# MJoy16-C1.net
KiCad netlist of a schematic drawn in EAGLE
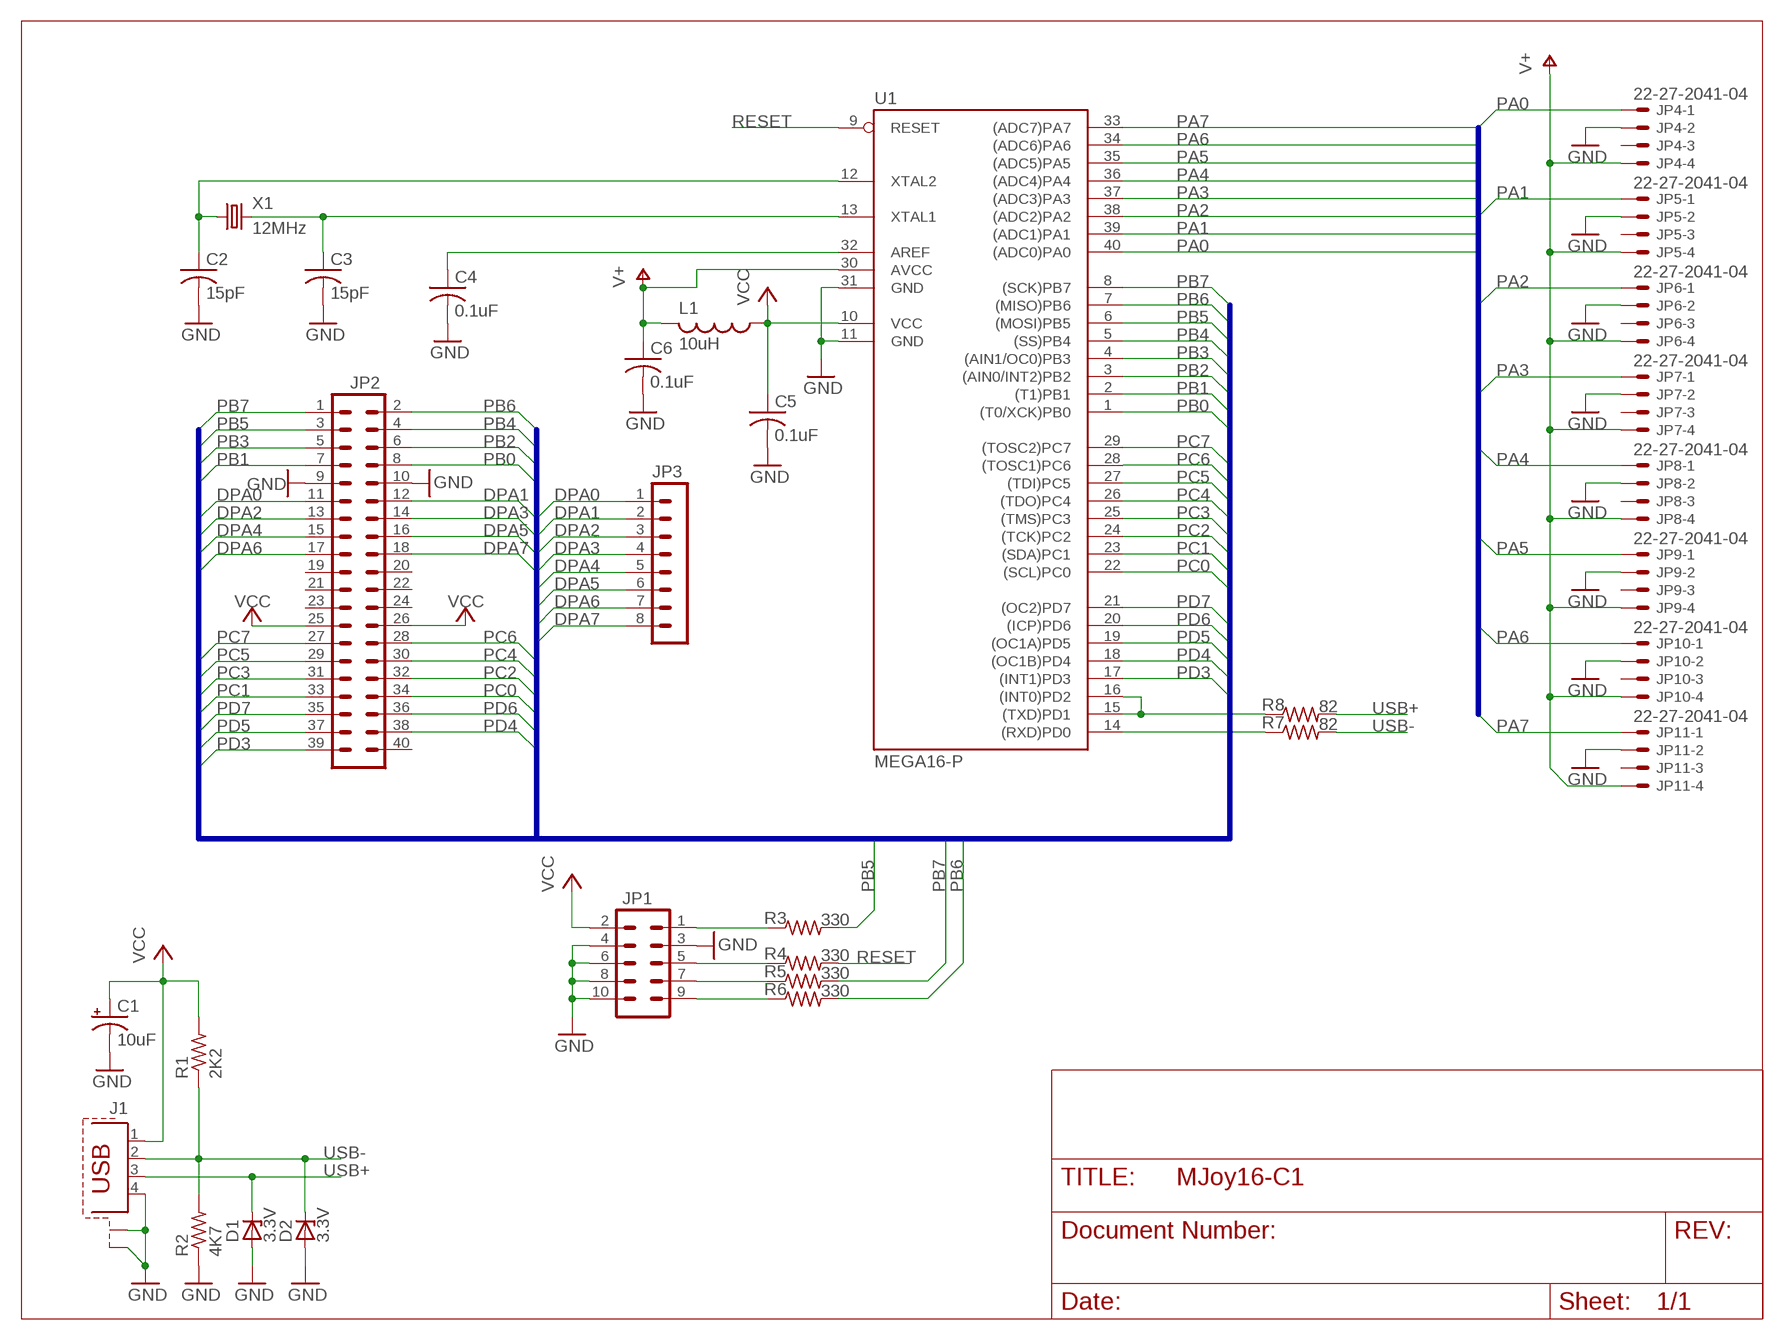
[diagram p0: schematic, sheet 1]

(export (version "E")
  (design (tool "Eeschema 10.0.6"))
  (components
    (comp (ref "C1")
      (value "10uF")
      (footprint "eagle-import:E2,5-5")
      (libsource (lib "eagle-import") (part "CPOL-USE2.5-5"))
    )
    (comp (ref "C2")
      (value "15pF")
      (footprint "eagle-import:C025-024X044")
      (libsource (lib "eagle-import") (part "C-US025-024X044"))
    )
    (comp (ref "C3")
      (value "15pF")
      (footprint "eagle-import:C025-024X044")
      (libsource (lib "eagle-import") (part "C-US025-024X044"))
    )
    (comp (ref "C4")
      (value "0.1uF")
      (footprint "eagle-import:C050-025X075")
      (libsource (lib "eagle-import") (part "C-US050-025X075"))
    )
    (comp (ref "C5")
      (value "0.1uF")
      (footprint "eagle-import:C050-025X075")
      (libsource (lib "eagle-import") (part "C-US050-025X075"))
    )
    (comp (ref "C6")
      (value "0.1uF")
      (footprint "eagle-import:C050-025X075")
      (libsource (lib "eagle-import") (part "C-US050-025X075"))
    )
    (comp (ref "D1")
      (value "3.3V")
      (footprint "eagle-import:ZDIO-5")
      (libsource (lib "eagle-import") (part "ZENER-DIODEZD-5"))
    )
    (comp (ref "D2")
      (value "3.3V")
      (footprint "eagle-import:ZDIO-5")
      (libsource (lib "eagle-import") (part "ZENER-DIODEZD-5"))
    )
    (comp (ref "J1")
      (value "PN61729-S")
      (footprint "eagle-import:PN61729-S")
      (libsource (lib "eagle-import") (part "PN61729-S"))
    )
    (comp (ref "JP1")
      (value "ML10")
      (footprint "eagle-import:ML10")
      (libsource (lib "eagle-import") (part "ML10"))
    )
    (comp (ref "JP2")
      (value "MA20-2")
      (footprint "eagle-import:MA20-2")
      (libsource (lib "eagle-import") (part "MA20-2"))
    )
    (comp (ref "JP3")
      (value "MA08-1")
      (footprint "eagle-import:MA08-1")
      (libsource (lib "eagle-import") (part "MA08-1"))
    )
    (comp (ref "JP4")
      (value "22-27-2041-04")
      (footprint "eagle-import:6410-04")
      (libsource (lib "eagle-import") (part "22-?-0427-2041"))
    )
    (comp (ref "JP5")
      (value "22-27-2041-04")
      (footprint "eagle-import:6410-04")
      (libsource (lib "eagle-import") (part "22-?-0427-2041"))
    )
    (comp (ref "JP6")
      (value "22-27-2041-04")
      (footprint "eagle-import:6410-04")
      (libsource (lib "eagle-import") (part "22-?-0427-2041"))
    )
    (comp (ref "JP7")
      (value "22-27-2041-04")
      (footprint "eagle-import:6410-04")
      (libsource (lib "eagle-import") (part "22-?-0427-2041"))
    )
    (comp (ref "JP8")
      (value "22-27-2041-04")
      (footprint "eagle-import:6410-04")
      (libsource (lib "eagle-import") (part "22-?-0427-2041"))
    )
    (comp (ref "JP9")
      (value "22-27-2041-04")
      (footprint "eagle-import:6410-04")
      (libsource (lib "eagle-import") (part "22-?-0427-2041"))
    )
    (comp (ref "JP10")
      (value "22-27-2041-04")
      (footprint "eagle-import:6410-04")
      (libsource (lib "eagle-import") (part "22-?-0427-2041"))
    )
    (comp (ref "JP11")
      (value "22-27-2041-04")
      (footprint "eagle-import:6410-04")
      (libsource (lib "eagle-import") (part "22-?-0427-2041"))
    )
    (comp (ref "L1")
      (value "10uH")
      (footprint "eagle-import:0207_7")
      (libsource (lib "eagle-import") (part "L-US0207/7"))
    )
    (comp (ref "R1")
      (value "2K2")
      (footprint "eagle-import:0207_7")
      (libsource (lib "eagle-import") (part "R-US_0207/7"))
    )
    (comp (ref "R2")
      (value "4K7")
      (footprint "eagle-import:0207_7")
      (libsource (lib "eagle-import") (part "R-US_0207/7"))
    )
    (comp (ref "R3")
      (value "330")
      (footprint "eagle-import:0207_7")
      (libsource (lib "eagle-import") (part "R-US_0207/7"))
    )
    (comp (ref "R4")
      (value "330")
      (footprint "eagle-import:0207_7")
      (libsource (lib "eagle-import") (part "R-US_0207/7"))
    )
    (comp (ref "R5")
      (value "330")
      (footprint "eagle-import:0207_7")
      (libsource (lib "eagle-import") (part "R-US_0207/7"))
    )
    (comp (ref "R6")
      (value "330")
      (footprint "eagle-import:0207_7")
      (libsource (lib "eagle-import") (part "R-US_0207/7"))
    )
    (comp (ref "R7")
      (value "82")
      (footprint "eagle-import:0207_7")
      (libsource (lib "eagle-import") (part "R-US_0207/7"))
    )
    (comp (ref "R8")
      (value "82")
      (footprint "eagle-import:0207_7")
      (libsource (lib "eagle-import") (part "R-US_0207/7"))
    )
    (comp (ref "U1")
      (value "MEGA16-P")
      (footprint "eagle-import:DIL40")
      (fields (field (name "MPN") "ATMEGA16-16PU"))
      (libsource (lib "eagle-import") (part "MEGA16-P"))
    )
    (comp (ref "X1")
      (value "12MHz")
      (footprint "eagle-import:HC49U-V")
      (libsource (lib "eagle-import") (part "CRYSTALHC49U-V"))
    )
  )
  (nets
    (net (code "1") (name "/DPA0") (class "Default")
      (node (ref "JP2") (pin "11") (pinfunction "11_11") (pintype "passive"))
      (node (ref "JP3") (pin "1") (pinfunction "1_1") (pintype "passive"))
    )
    (net (code "2") (name "/DPA1") (class "Default")
      (node (ref "JP2") (pin "12") (pinfunction "12_12") (pintype "passive"))
      (node (ref "JP3") (pin "2") (pinfunction "2_2") (pintype "passive"))
    )
    (net (code "3") (name "/DPA2") (class "Default")
      (node (ref "JP2") (pin "13") (pinfunction "13_13") (pintype "passive"))
      (node (ref "JP3") (pin "3") (pinfunction "3_3") (pintype "passive"))
    )
    (net (code "4") (name "/DPA3") (class "Default")
      (node (ref "JP2") (pin "14") (pinfunction "14_14") (pintype "passive"))
      (node (ref "JP3") (pin "4") (pinfunction "4_4") (pintype "passive"))
    )
    (net (code "5") (name "/DPA4") (class "Default")
      (node (ref "JP2") (pin "15") (pinfunction "15_15") (pintype "passive"))
      (node (ref "JP3") (pin "5") (pinfunction "5_5") (pintype "passive"))
    )
    (net (code "6") (name "/DPA5") (class "Default")
      (node (ref "JP2") (pin "16") (pinfunction "16_16") (pintype "passive"))
      (node (ref "JP3") (pin "6") (pinfunction "6_6") (pintype "passive"))
    )
    (net (code "7") (name "/DPA6") (class "Default")
      (node (ref "JP2") (pin "17") (pinfunction "17_17") (pintype "passive"))
      (node (ref "JP3") (pin "7") (pinfunction "7_7") (pintype "passive"))
    )
    (net (code "8") (name "/DPA7") (class "Default")
      (node (ref "JP2") (pin "18") (pinfunction "18_18") (pintype "passive"))
      (node (ref "JP3") (pin "8") (pinfunction "8_8") (pintype "passive"))
    )
    (net (code "9") (name "/PA0") (class "Default")
      (node (ref "JP4") (pin "1") (pinfunction "S_1") (pintype "passive"))
      (node (ref "U1") (pin "40") (pinfunction "(ADC0)PA0_40") (pintype "bidirectional"))
    )
    (net (code "10") (name "/PA1") (class "Default")
      (node (ref "JP5") (pin "1") (pinfunction "S_1") (pintype "passive"))
      (node (ref "U1") (pin "39") (pinfunction "(ADC1)PA1_39") (pintype "bidirectional"))
    )
    (net (code "11") (name "/PA2") (class "Default")
      (node (ref "JP6") (pin "1") (pinfunction "S_1") (pintype "passive"))
      (node (ref "U1") (pin "38") (pinfunction "(ADC2)PA2_38") (pintype "bidirectional"))
    )
    (net (code "12") (name "/PA3") (class "Default")
      (node (ref "JP7") (pin "1") (pinfunction "S_1") (pintype "passive"))
      (node (ref "U1") (pin "37") (pinfunction "(ADC3)PA3_37") (pintype "bidirectional"))
    )
    (net (code "13") (name "/PA4") (class "Default")
      (node (ref "JP8") (pin "1") (pinfunction "S_1") (pintype "passive"))
      (node (ref "U1") (pin "36") (pinfunction "(ADC4)PA4_36") (pintype "bidirectional"))
    )
    (net (code "14") (name "/PA5") (class "Default")
      (node (ref "JP9") (pin "1") (pinfunction "S_1") (pintype "passive"))
      (node (ref "U1") (pin "35") (pinfunction "(ADC5)PA5_35") (pintype "bidirectional"))
    )
    (net (code "15") (name "/PA6") (class "Default")
      (node (ref "JP10") (pin "1") (pinfunction "S_1") (pintype "passive"))
      (node (ref "U1") (pin "34") (pinfunction "(ADC6)PA6_34") (pintype "bidirectional"))
    )
    (net (code "16") (name "/PA7") (class "Default")
      (node (ref "JP11") (pin "1") (pinfunction "S_1") (pintype "passive"))
      (node (ref "U1") (pin "33") (pinfunction "(ADC7)PA7_33") (pintype "bidirectional"))
    )
    (net (code "17") (name "/PB0") (class "Default")
      (node (ref "JP2") (pin "8") (pinfunction "8_8") (pintype "passive"))
      (node (ref "U1") (pin "1") (pinfunction "(T0/XCK)PB0_1") (pintype "bidirectional"))
    )
    (net (code "18") (name "/PB1") (class "Default")
      (node (ref "JP2") (pin "7") (pinfunction "7_7") (pintype "passive"))
      (node (ref "U1") (pin "2") (pinfunction "(T1)PB1_2") (pintype "bidirectional"))
    )
    (net (code "19") (name "/PB2") (class "Default")
      (node (ref "JP2") (pin "6") (pinfunction "6_6") (pintype "passive"))
      (node (ref "U1") (pin "3") (pinfunction "(AIN0/INT2)PB2_3") (pintype "bidirectional"))
    )
    (net (code "20") (name "/PB3") (class "Default")
      (node (ref "JP2") (pin "5") (pinfunction "5_5") (pintype "passive"))
      (node (ref "U1") (pin "4") (pinfunction "(AIN1/OC0)PB3_4") (pintype "bidirectional"))
    )
    (net (code "21") (name "/PB4") (class "Default")
      (node (ref "JP2") (pin "4") (pinfunction "4_4") (pintype "passive"))
      (node (ref "U1") (pin "5") (pinfunction "(SS)PB4_5") (pintype "bidirectional"))
    )
    (net (code "22") (name "/PB5") (class "Default")
      (node (ref "JP2") (pin "3") (pinfunction "3_3") (pintype "passive"))
      (node (ref "R3") (pin "2") (pinfunction "2_2") (pintype "passive"))
      (node (ref "U1") (pin "6") (pinfunction "(MOSI)PB5_6") (pintype "bidirectional"))
    )
    (net (code "23") (name "/PB6") (class "Default")
      (node (ref "JP2") (pin "2") (pinfunction "2_2") (pintype "passive"))
      (node (ref "R6") (pin "2") (pinfunction "2_2") (pintype "passive"))
      (node (ref "U1") (pin "7") (pinfunction "(MISO)PB6_7") (pintype "bidirectional"))
    )
    (net (code "24") (name "/PB7") (class "Default")
      (node (ref "JP2") (pin "1") (pinfunction "1_1") (pintype "passive"))
      (node (ref "R5") (pin "2") (pinfunction "2_2") (pintype "passive"))
      (node (ref "U1") (pin "8") (pinfunction "(SCK)PB7_8") (pintype "bidirectional"))
    )
    (net (code "25") (name "/PC0") (class "Default")
      (node (ref "JP2") (pin "34") (pinfunction "34_34") (pintype "passive"))
      (node (ref "U1") (pin "22") (pinfunction "(SCL)PC0_22") (pintype "bidirectional"))
    )
    (net (code "26") (name "/PC1") (class "Default")
      (node (ref "JP2") (pin "33") (pinfunction "33_33") (pintype "passive"))
      (node (ref "U1") (pin "23") (pinfunction "(SDA)PC1_23") (pintype "bidirectional"))
    )
    (net (code "27") (name "/PC2") (class "Default")
      (node (ref "JP2") (pin "32") (pinfunction "32_32") (pintype "passive"))
      (node (ref "U1") (pin "24") (pinfunction "(TCK)PC2_24") (pintype "bidirectional"))
    )
    (net (code "28") (name "/PC3") (class "Default")
      (node (ref "JP2") (pin "31") (pinfunction "31_31") (pintype "passive"))
      (node (ref "U1") (pin "25") (pinfunction "(TMS)PC3_25") (pintype "bidirectional"))
    )
    (net (code "29") (name "/PC4") (class "Default")
      (node (ref "JP2") (pin "30") (pinfunction "30_30") (pintype "passive"))
      (node (ref "U1") (pin "26") (pinfunction "(TDO)PC4_26") (pintype "bidirectional"))
    )
    (net (code "30") (name "/PC5") (class "Default")
      (node (ref "JP2") (pin "29") (pinfunction "29_29") (pintype "passive"))
      (node (ref "U1") (pin "27") (pinfunction "(TDI)PC5_27") (pintype "bidirectional"))
    )
    (net (code "31") (name "/PC6") (class "Default")
      (node (ref "JP2") (pin "28") (pinfunction "28_28") (pintype "passive"))
      (node (ref "U1") (pin "28") (pinfunction "(TOSC1)PC6_28") (pintype "bidirectional"))
    )
    (net (code "32") (name "/PC7") (class "Default")
      (node (ref "JP2") (pin "27") (pinfunction "27_27") (pintype "passive"))
      (node (ref "U1") (pin "29") (pinfunction "(TOSC2)PC7_29") (pintype "bidirectional"))
    )
    (net (code "33") (name "/PD3") (class "Default")
      (node (ref "JP2") (pin "39") (pinfunction "39_39") (pintype "passive"))
      (node (ref "U1") (pin "17") (pinfunction "(INT1)PD3_17") (pintype "bidirectional"))
    )
    (net (code "34") (name "/PD4") (class "Default")
      (node (ref "JP2") (pin "38") (pinfunction "38_38") (pintype "passive"))
      (node (ref "U1") (pin "18") (pinfunction "(OC1B)PD4_18") (pintype "bidirectional"))
    )
    (net (code "35") (name "/PD5") (class "Default")
      (node (ref "JP2") (pin "37") (pinfunction "37_37") (pintype "passive"))
      (node (ref "U1") (pin "19") (pinfunction "(OC1A)PD5_19") (pintype "bidirectional"))
    )
    (net (code "36") (name "/PD6") (class "Default")
      (node (ref "JP2") (pin "36") (pinfunction "36_36") (pintype "passive"))
      (node (ref "U1") (pin "20") (pinfunction "(ICP)PD6_20") (pintype "bidirectional"))
    )
    (net (code "37") (name "/PD7") (class "Default")
      (node (ref "JP2") (pin "35") (pinfunction "35_35") (pintype "passive"))
      (node (ref "U1") (pin "21") (pinfunction "(OC2)PD7_21") (pintype "bidirectional"))
    )
    (net (code "38") (name "/RESET") (class "Default")
      (node (ref "R4") (pin "2") (pinfunction "2_2") (pintype "passive"))
      (node (ref "U1") (pin "9") (pinfunction "RESET_9") (pintype "input"))
    )
    (net (code "39") (name "/USB+") (class "Default")
      (node (ref "D1") (pin "C") (pinfunction "C_C") (pintype "passive"))
      (node (ref "J1") (pin "3") (pinfunction "3_3") (pintype "passive"))
      (node (ref "R8") (pin "2") (pinfunction "2_2") (pintype "passive"))
    )
    (net (code "40") (name "/USB-") (class "Default")
      (node (ref "D2") (pin "C") (pinfunction "C_C") (pintype "passive"))
      (node (ref "J1") (pin "2") (pinfunction "2_2") (pintype "passive"))
      (node (ref "R1") (pin "1") (pinfunction "1_1") (pintype "passive"))
      (node (ref "R2") (pin "2") (pinfunction "2_2") (pintype "passive"))
      (node (ref "R7") (pin "2") (pinfunction "2_2") (pintype "passive"))
    )
    (net (code "41") (name "GND") (class "Default")
      (node (ref "C1") (pin "-") (pinfunction "-_-") (pintype "passive"))
      (node (ref "C2") (pin "2") (pinfunction "2_2") (pintype "passive"))
      (node (ref "C3") (pin "2") (pinfunction "2_2") (pintype "passive"))
      (node (ref "C4") (pin "2") (pinfunction "2_2") (pintype "passive"))
      (node (ref "C5") (pin "2") (pinfunction "2_2") (pintype "passive"))
      (node (ref "C6") (pin "2") (pinfunction "2_2") (pintype "passive"))
      (node (ref "D1") (pin "A") (pinfunction "A_A") (pintype "passive"))
      (node (ref "D2") (pin "A") (pinfunction "A_A") (pintype "passive"))
      (node (ref "J1") (pin "4") (pinfunction "4_4") (pintype "passive"))
      (node (ref "J1") (pin "S1") (pinfunction "S1_S1") (pintype "passive"))
      (node (ref "J1") (pin "S2") (pinfunction "S2_S2") (pintype "passive"))
      (node (ref "JP1") (pin "10") (pinfunction "10_10") (pintype "passive"))
      (node (ref "JP1") (pin "3") (pinfunction "3_3") (pintype "passive"))
      (node (ref "JP1") (pin "4") (pinfunction "4_4") (pintype "passive"))
      (node (ref "JP1") (pin "6") (pinfunction "6_6") (pintype "passive"))
      (node (ref "JP1") (pin "8") (pinfunction "8_8") (pintype "passive"))
      (node (ref "JP10") (pin "2") (pinfunction "S_2") (pintype "passive"))
      (node (ref "JP11") (pin "2") (pinfunction "S_2") (pintype "passive"))
      (node (ref "JP2") (pin "10") (pinfunction "10_10") (pintype "passive"))
      (node (ref "JP2") (pin "9") (pinfunction "9_9") (pintype "passive"))
      (node (ref "JP4") (pin "2") (pinfunction "S_2") (pintype "passive"))
      (node (ref "JP5") (pin "2") (pinfunction "S_2") (pintype "passive"))
      (node (ref "JP6") (pin "2") (pinfunction "S_2") (pintype "passive"))
      (node (ref "JP7") (pin "2") (pinfunction "S_2") (pintype "passive"))
      (node (ref "JP8") (pin "2") (pinfunction "S_2") (pintype "passive"))
      (node (ref "JP9") (pin "2") (pinfunction "S_2") (pintype "passive"))
      (node (ref "R2") (pin "1") (pinfunction "1_1") (pintype "passive"))
      (node (ref "U1") (pin "11") (pinfunction "GND_11") (pintype "power_in"))
      (node (ref "U1") (pin "31") (pinfunction "GND_31") (pintype "power_in"))
    )
    (net (code "42") (name "Net-(JP1-Pad1)") (class "Default")
      (node (ref "JP1") (pin "1") (pinfunction "1_1") (pintype "passive"))
      (node (ref "R3") (pin "1") (pinfunction "1_1") (pintype "passive"))
    )
    (net (code "43") (name "Net-(JP1-Pad5)") (class "Default")
      (node (ref "JP1") (pin "5") (pinfunction "5_5") (pintype "passive"))
      (node (ref "R4") (pin "1") (pinfunction "1_1") (pintype "passive"))
    )
    (net (code "44") (name "Net-(JP1-Pad7)") (class "Default")
      (node (ref "JP1") (pin "7") (pinfunction "7_7") (pintype "passive"))
      (node (ref "R5") (pin "1") (pinfunction "1_1") (pintype "passive"))
    )
    (net (code "45") (name "Net-(JP1-Pad9)") (class "Default")
      (node (ref "JP1") (pin "9") (pinfunction "9_9") (pintype "passive"))
      (node (ref "R6") (pin "1") (pinfunction "1_1") (pintype "passive"))
    )
    (net (code "46") (name "Net-(U1-(INT0)PD2)") (class "Default")
      (node (ref "R8") (pin "1") (pinfunction "1_1") (pintype "passive"))
      (node (ref "U1") (pin "15") (pinfunction "(TXD)PD1_15") (pintype "bidirectional"))
      (node (ref "U1") (pin "16") (pinfunction "(INT0)PD2_16") (pintype "bidirectional"))
    )
    (net (code "47") (name "Net-(U1-(RXD)PD0)") (class "Default")
      (node (ref "R7") (pin "1") (pinfunction "1_1") (pintype "passive"))
      (node (ref "U1") (pin "14") (pinfunction "(RXD)PD0_14") (pintype "bidirectional"))
    )
    (net (code "48") (name "Net-(U1-AREF)") (class "Default")
      (node (ref "C4") (pin "1") (pinfunction "1_1") (pintype "passive"))
      (node (ref "U1") (pin "32") (pinfunction "AREF_32") (pintype "passive"))
    )
    (net (code "49") (name "Net-(U1-XTAL1)") (class "Default")
      (node (ref "C3") (pin "1") (pinfunction "1_1") (pintype "passive"))
      (node (ref "U1") (pin "13") (pinfunction "XTAL1_13") (pintype "bidirectional"))
      (node (ref "X1") (pin "2") (pinfunction "2_2") (pintype "passive"))
    )
    (net (code "50") (name "Net-(U1-XTAL2)") (class "Default")
      (node (ref "C2") (pin "1") (pinfunction "1_1") (pintype "passive"))
      (node (ref "U1") (pin "12") (pinfunction "XTAL2_12") (pintype "bidirectional"))
      (node (ref "X1") (pin "1") (pinfunction "1_1") (pintype "passive"))
    )
    (net (code "51") (name "V+") (class "Default")
      (node (ref "C6") (pin "1") (pinfunction "1_1") (pintype "passive"))
      (node (ref "JP10") (pin "4") (pinfunction "S_4") (pintype "passive"))
      (node (ref "JP11") (pin "4") (pinfunction "S_4") (pintype "passive"))
      (node (ref "JP4") (pin "4") (pinfunction "S_4") (pintype "passive"))
      (node (ref "JP5") (pin "4") (pinfunction "S_4") (pintype "passive"))
      (node (ref "JP6") (pin "4") (pinfunction "S_4") (pintype "passive"))
      (node (ref "JP7") (pin "4") (pinfunction "S_4") (pintype "passive"))
      (node (ref "JP8") (pin "4") (pinfunction "S_4") (pintype "passive"))
      (node (ref "JP9") (pin "4") (pinfunction "S_4") (pintype "passive"))
      (node (ref "L1") (pin "2") (pinfunction "2_2") (pintype "passive"))
      (node (ref "U1") (pin "30") (pinfunction "AVCC_30") (pintype "power_in"))
    )
    (net (code "52") (name "VCC") (class "Default")
      (node (ref "C1") (pin "+") (pinfunction "+_+") (pintype "passive"))
      (node (ref "C5") (pin "1") (pinfunction "1_1") (pintype "passive"))
      (node (ref "J1") (pin "1") (pinfunction "1_1") (pintype "passive"))
      (node (ref "JP1") (pin "2") (pinfunction "2_2") (pintype "passive"))
      (node (ref "JP2") (pin "25") (pinfunction "25_25") (pintype "passive"))
      (node (ref "JP2") (pin "26") (pinfunction "26_26") (pintype "passive"))
      (node (ref "L1") (pin "1") (pinfunction "1_1") (pintype "passive"))
      (node (ref "R1") (pin "2") (pinfunction "2_2") (pintype "passive"))
      (node (ref "U1") (pin "10") (pinfunction "VCC_10") (pintype "power_in"))
    )
    (net (code "53") (name "unconnected-(JP2-Pad19)") (class "Default")
      (node (ref "JP2") (pin "19") (pinfunction "19_19") (pintype "passive"))
    )
    (net (code "54") (name "unconnected-(JP2-Pad20)") (class "Default")
      (node (ref "JP2") (pin "20") (pinfunction "20_20") (pintype "passive"))
    )
    (net (code "55") (name "unconnected-(JP2-Pad21)") (class "Default")
      (node (ref "JP2") (pin "21") (pinfunction "21_21") (pintype "passive"))
    )
    (net (code "56") (name "unconnected-(JP2-Pad22)") (class "Default")
      (node (ref "JP2") (pin "22") (pinfunction "22_22") (pintype "passive"))
    )
    (net (code "57") (name "unconnected-(JP2-Pad23)") (class "Default")
      (node (ref "JP2") (pin "23") (pinfunction "23_23") (pintype "passive"))
    )
    (net (code "58") (name "unconnected-(JP2-Pad24)") (class "Default")
      (node (ref "JP2") (pin "24") (pinfunction "24_24") (pintype "passive"))
    )
    (net (code "59") (name "unconnected-(JP2-Pad40)") (class "Default")
      (node (ref "JP2") (pin "40") (pinfunction "40_40") (pintype "passive"))
    )
    (net (code "60") (name "unconnected-(JP4C-S-Pad3)") (class "Default")
      (node (ref "JP4") (pin "3") (pinfunction "S_3") (pintype "passive"))
    )
    (net (code "61") (name "unconnected-(JP5C-S-Pad3)") (class "Default")
      (node (ref "JP5") (pin "3") (pinfunction "S_3") (pintype "passive"))
    )
    (net (code "62") (name "unconnected-(JP6C-S-Pad3)") (class "Default")
      (node (ref "JP6") (pin "3") (pinfunction "S_3") (pintype "passive"))
    )
    (net (code "63") (name "unconnected-(JP7C-S-Pad3)") (class "Default")
      (node (ref "JP7") (pin "3") (pinfunction "S_3") (pintype "passive"))
    )
    (net (code "64") (name "unconnected-(JP8C-S-Pad3)") (class "Default")
      (node (ref "JP8") (pin "3") (pinfunction "S_3") (pintype "passive"))
    )
    (net (code "65") (name "unconnected-(JP9C-S-Pad3)") (class "Default")
      (node (ref "JP9") (pin "3") (pinfunction "S_3") (pintype "passive"))
    )
    (net (code "66") (name "unconnected-(JP10C-S-Pad3)") (class "Default")
      (node (ref "JP10") (pin "3") (pinfunction "S_3") (pintype "passive"))
    )
    (net (code "67") (name "unconnected-(JP11C-S-Pad3)") (class "Default")
      (node (ref "JP11") (pin "3") (pinfunction "S_3") (pintype "passive"))
    )
  )
)
